# MCU.net
KiCad netlist of a schematic drawn in Altium Designer
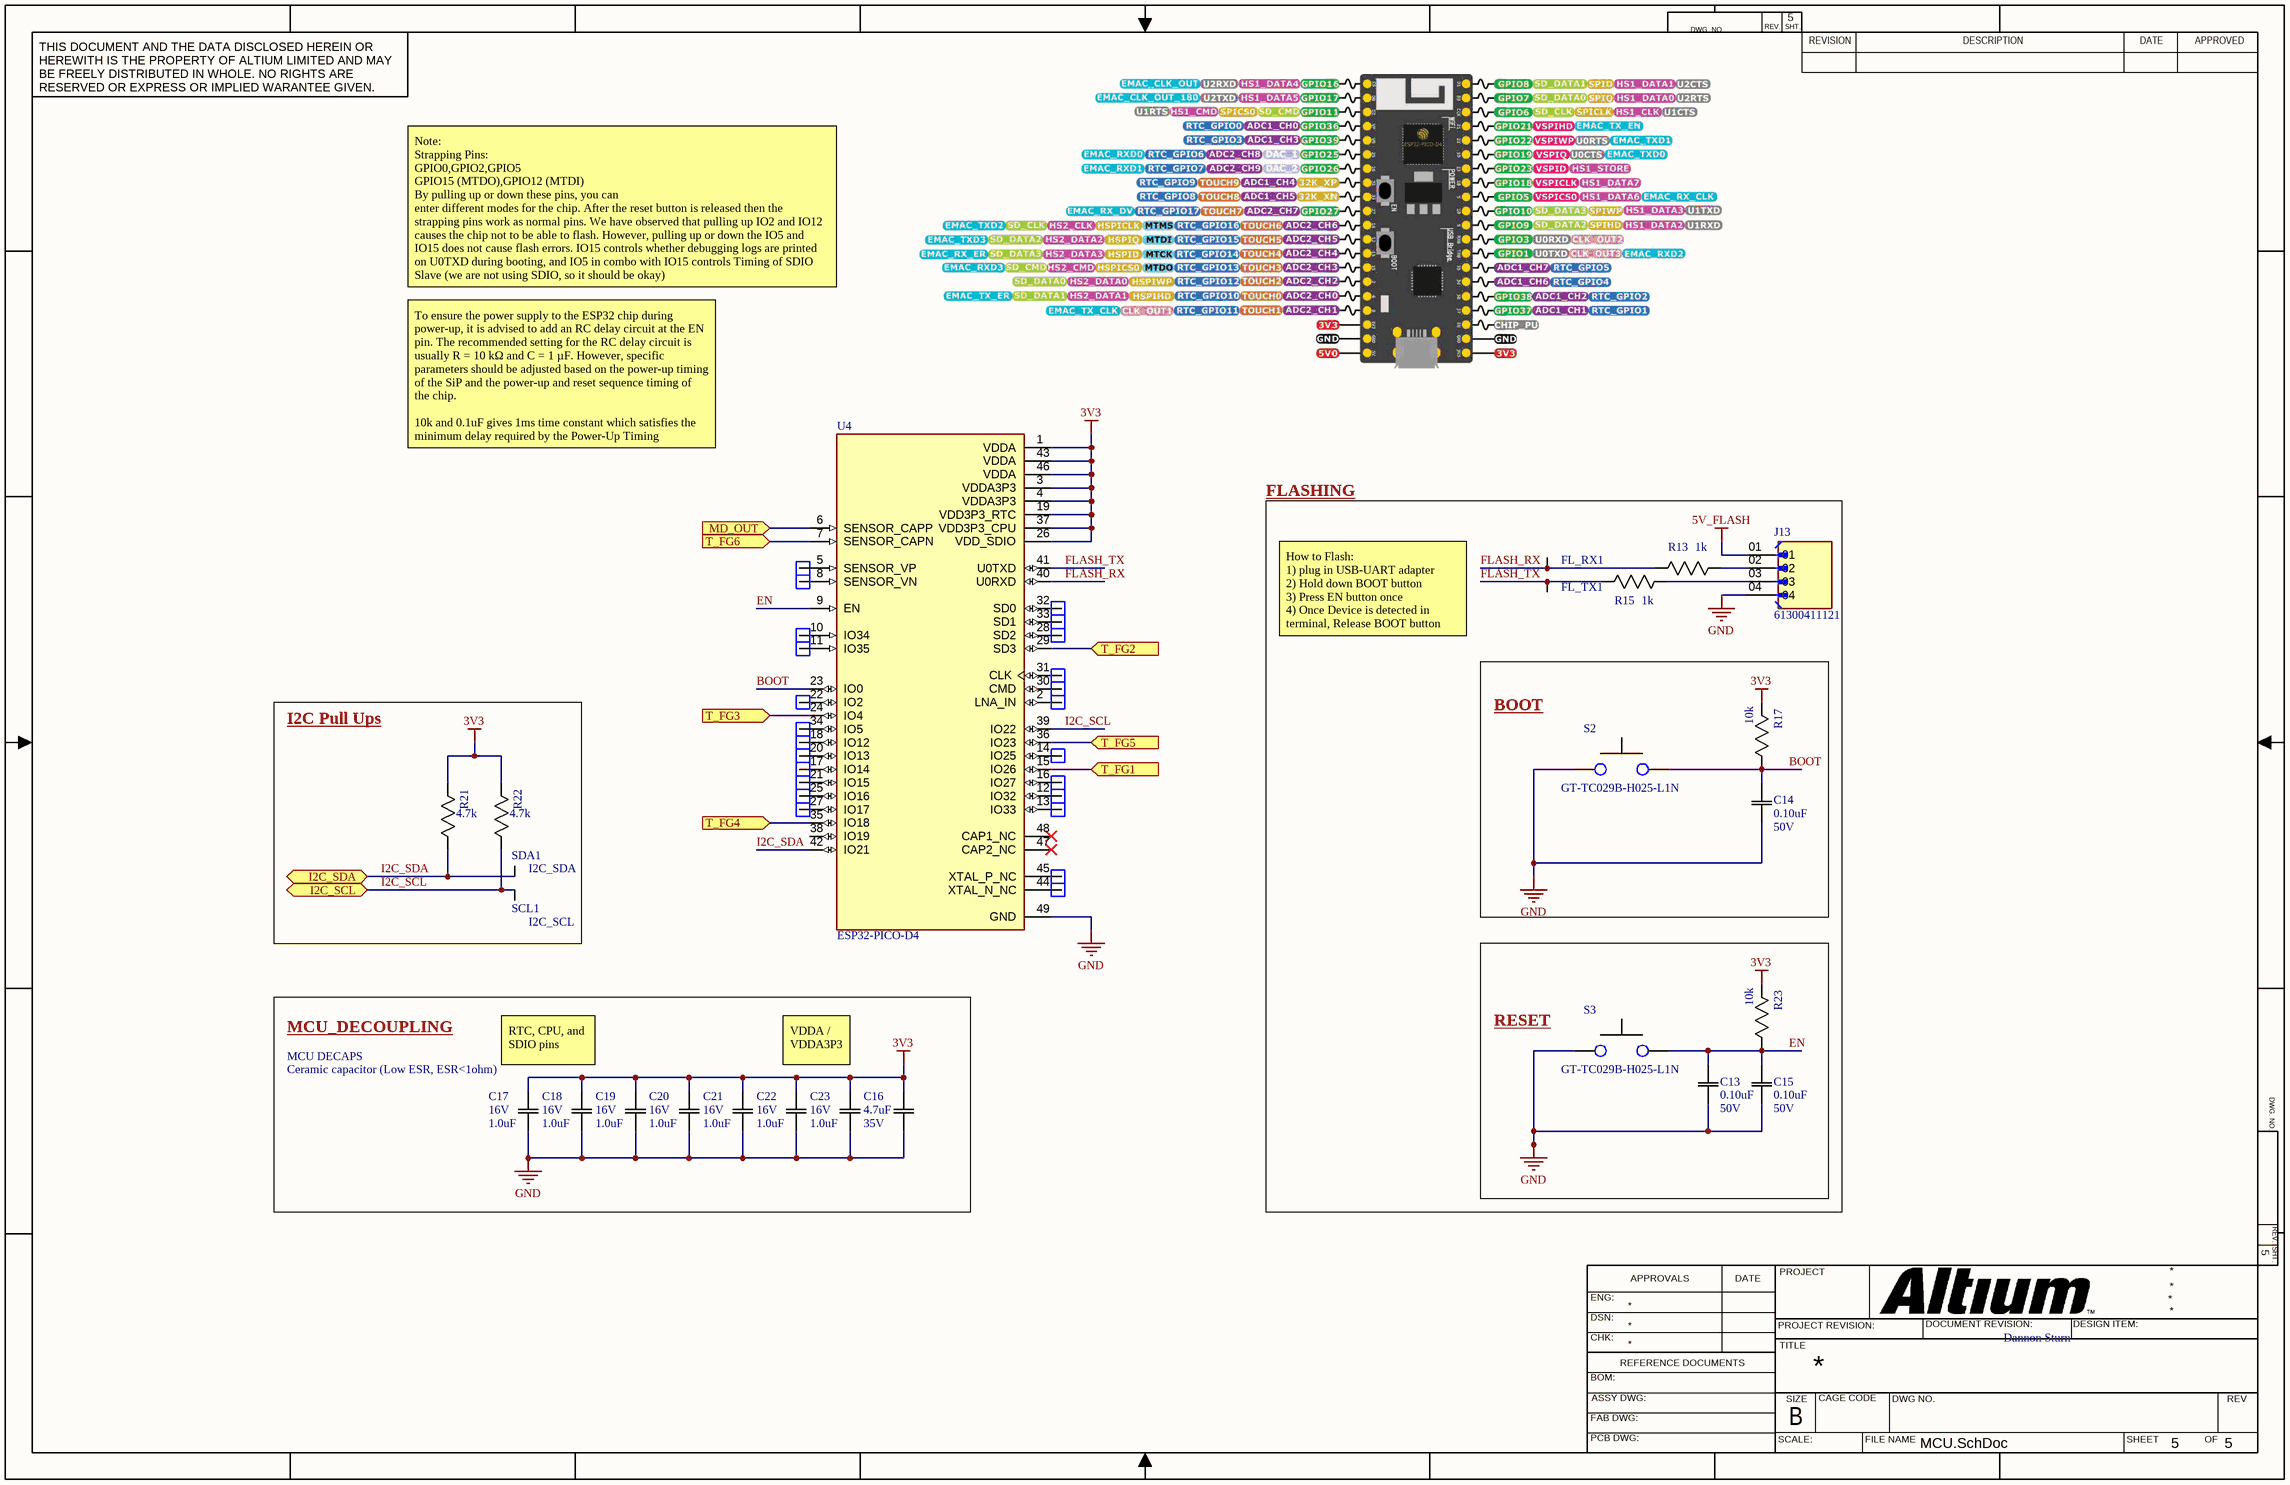
[diagram p0: MCU.SchDoc]

(export (version "E")
  (design (tool "Eeschema 10.0.6"))
  (components
    (comp (ref "1")
      (value "Breakout Pin 0603")
      (footprint "BreakoutPin 0603")
      (description "0603 breakout pad")
      (libsource (lib "IC_Library") (part "Breakout Pin 0603"))
    )
    (comp (ref "2")
      (value "Breakout Pin 0603")
      (footprint "BreakoutPin 0603")
      (description "0603 breakout pad")
      (libsource (lib "IC_Library") (part "Breakout Pin 0603"))
    )
    (comp (ref "3")
      (value "Breakout Pin 0603")
      (footprint "BreakoutPin 0603")
      (description "0603 breakout pad")
      (libsource (lib "IC_Library") (part "Breakout Pin 0603"))
    )
    (comp (ref "4")
      (value "Breakout Pin 0603")
      (footprint "BreakoutPin 0603")
      (description "0603 breakout pad")
      (libsource (lib "IC_Library") (part "Breakout Pin 0603"))
    )
    (comp (ref "5")
      (value "Breakout Pin 0603")
      (footprint "BreakoutPin 0603")
      (description "0603 breakout pad")
      (libsource (lib "IC_Library") (part "Breakout Pin 0603"))
    )
    (comp (ref "6")
      (value "Breakout Pin 0603")
      (footprint "BreakoutPin 0603")
      (description "0603 breakout pad")
      (libsource (lib "IC_Library") (part "Breakout Pin 0603"))
    )
    (comp (ref "7")
      (value "Breakout Pin 0603")
      (footprint "BreakoutPin 0603")
      (description "0603 breakout pad")
      (libsource (lib "IC_Library") (part "Breakout Pin 0603"))
    )
    (comp (ref "8")
      (value "Breakout Pin 0603")
      (footprint "BreakoutPin 0603")
      (description "0603 breakout pad")
      (libsource (lib "IC_Library") (part "Breakout Pin 0603"))
    )
    (comp (ref "9")
      (value "Breakout Pin 0603")
      (footprint "BreakoutPin 0603")
      (description "0603 breakout pad")
      (libsource (lib "IC_Library") (part "Breakout Pin 0603"))
    )
    (comp (ref "10")
      (value "Breakout Pin 0603")
      (footprint "BreakoutPin 0603")
      (description "0603 breakout pad")
      (libsource (lib "IC_Library") (part "Breakout Pin 0603"))
    )
    (comp (ref "11")
      (value "Breakout Pin 0603")
      (footprint "BreakoutPin 0603")
      (description "0603 breakout pad")
      (libsource (lib "IC_Library") (part "Breakout Pin 0603"))
    )
    (comp (ref "12")
      (value "Breakout Pin 0603")
      (footprint "BreakoutPin 0603")
      (description "0603 breakout pad")
      (libsource (lib "IC_Library") (part "Breakout Pin 0603"))
    )
    (comp (ref "13")
      (value "Breakout Pin 0603")
      (footprint "BreakoutPin 0603")
      (description "0603 breakout pad")
      (libsource (lib "IC_Library") (part "Breakout Pin 0603"))
    )
    (comp (ref "14")
      (value "Breakout Pin 0603")
      (footprint "BreakoutPin 0603")
      (description "0603 breakout pad")
      (libsource (lib "IC_Library") (part "Breakout Pin 0603"))
    )
    (comp (ref "15")
      (value "Breakout Pin 0603")
      (footprint "BreakoutPin 0603")
      (description "0603 breakout pad")
      (libsource (lib "IC_Library") (part "Breakout Pin 0603"))
    )
    (comp (ref "16")
      (value "Breakout Pin 0603")
      (footprint "BreakoutPin 0603")
      (description "0603 breakout pad")
      (libsource (lib "IC_Library") (part "Breakout Pin 0603"))
    )
    (comp (ref "17")
      (value "Breakout Pin 0603")
      (footprint "BreakoutPin 0603")
      (description "0603 breakout pad")
      (libsource (lib "IC_Library") (part "Breakout Pin 0603"))
    )
    (comp (ref "18")
      (value "Breakout Pin 0603")
      (footprint "BreakoutPin 0603")
      (description "0603 breakout pad")
      (libsource (lib "IC_Library") (part "Breakout Pin 0603"))
    )
    (comp (ref "19")
      (value "Breakout Pin 0603")
      (footprint "BreakoutPin 0603")
      (description "0603 breakout pad")
      (libsource (lib "IC_Library") (part "Breakout Pin 0603"))
    )
    (comp (ref "20")
      (value "Breakout Pin 0603")
      (footprint "BreakoutPin 0603")
      (description "0603 breakout pad")
      (libsource (lib "IC_Library") (part "Breakout Pin 0603"))
    )
    (comp (ref "21")
      (value "Breakout Pin 0603")
      (footprint "BreakoutPin 0603")
      (description "0603 breakout pad")
      (libsource (lib "IC_Library") (part "Breakout Pin 0603"))
    )
    (comp (ref "22")
      (value "Breakout Pin 0603")
      (footprint "BreakoutPin 0603")
      (description "0603 breakout pad")
      (libsource (lib "IC_Library") (part "Breakout Pin 0603"))
    )
    (comp (ref "23")
      (value "Breakout Pin 0603")
      (footprint "BreakoutPin 0603")
      (description "0603 breakout pad")
      (libsource (lib "IC_Library") (part "Breakout Pin 0603"))
    )
    (comp (ref "24")
      (value "Breakout Pin 0603")
      (footprint "BreakoutPin 0603")
      (description "0603 breakout pad")
      (libsource (lib "IC_Library") (part "Breakout Pin 0603"))
    )
    (comp (ref "C13")
      (value "0.10uF")
      (footprint "0603")
      (description "Default Symbol for Capacitors")
      (fields
        (field (name "RATING") "50V")
        (field (name "PART NUMBER") "CAP 0.1uF 50V")
        (field (name "TOLERANCE") "10%")
      )
      (libsource (lib "capacitor_library") (part "CAP_Default"))
    )
    (comp (ref "C14")
      (value "0.10uF")
      (footprint "0603")
      (description "Default Symbol for Capacitors")
      (fields
        (field (name "RATING") "50V")
        (field (name "PART NUMBER") "CAP 0.1uF 50V")
        (field (name "TOLERANCE") "10%")
      )
      (libsource (lib "capacitor_library") (part "CAP_Default"))
    )
    (comp (ref "C15")
      (value "0.10uF")
      (footprint "0805")
      (description "Default Symbol for Capacitors")
      (fields
        (field (name "RATING") "50V")
        (field (name "PART NUMBER") "CAP 0.1uF 50V")
        (field (name "TOLERANCE") "10%")
      )
      (libsource (lib "capacitor_library") (part "CAP_Default"))
    )
    (comp (ref "C16")
      (value "4.7uF")
      (footprint "0603")
      (description "CAP CER 4.7UF 35V X7R 0603/0805")
      (fields
        (field (name "TOLERANCE") "10%")
        (field (name "RATING") "35V")
        (field (name "PART NUMBER") "CAP 4.7uF 35V")
      )
      (libsource (lib "capacitor_library") (part "CAP 4.7uF 35V"))
    )
    (comp (ref "C17")
      (value "1.0uF")
      (footprint "0603")
      (description "CAP CER 1.0UF 16V X5R 0603/0805")
      (fields
        (field (name "TOLERANCE") "10%")
        (field (name "RATING") "16V")
        (field (name "PART NUMBER") "CAP 1.0uF 16V")
      )
      (libsource (lib "capacitor_library") (part "CAP 1.0uF 16V"))
    )
    (comp (ref "C18")
      (value "1.0uF")
      (footprint "0603")
      (description "CAP CER 1.0UF 16V X5R 0603/0805")
      (fields
        (field (name "TOLERANCE") "10%")
        (field (name "RATING") "16V")
        (field (name "PART NUMBER") "CAP 1.0uF 16V")
      )
      (libsource (lib "capacitor_library") (part "CAP 1.0uF 16V"))
    )
    (comp (ref "C19")
      (value "1.0uF")
      (footprint "0603")
      (description "CAP CER 1.0UF 16V X5R 0603/0805")
      (fields
        (field (name "TOLERANCE") "10%")
        (field (name "RATING") "16V")
        (field (name "PART NUMBER") "CAP 1.0uF 16V")
      )
      (libsource (lib "capacitor_library") (part "CAP 1.0uF 16V"))
    )
    (comp (ref "C20")
      (value "1.0uF")
      (footprint "0603")
      (description "CAP CER 1.0UF 16V X5R 0603/0805")
      (fields
        (field (name "TOLERANCE") "10%")
        (field (name "RATING") "16V")
        (field (name "PART NUMBER") "CAP 1.0uF 16V")
      )
      (libsource (lib "capacitor_library") (part "CAP 1.0uF 16V"))
    )
    (comp (ref "C21")
      (value "1.0uF")
      (footprint "0603")
      (description "CAP CER 1.0UF 16V X5R 0603/0805")
      (fields
        (field (name "TOLERANCE") "10%")
        (field (name "RATING") "16V")
        (field (name "PART NUMBER") "CAP 1.0uF 16V")
      )
      (libsource (lib "capacitor_library") (part "CAP 1.0uF 16V"))
    )
    (comp (ref "C22")
      (value "1.0uF")
      (footprint "0603")
      (description "CAP CER 1.0UF 16V X5R 0603/0805")
      (fields
        (field (name "TOLERANCE") "10%")
        (field (name "RATING") "16V")
        (field (name "PART NUMBER") "CAP 1.0uF 16V")
      )
      (libsource (lib "capacitor_library") (part "CAP 1.0uF 16V"))
    )
    (comp (ref "C23")
      (value "1.0uF")
      (footprint "0603")
      (description "CAP CER 1.0UF 16V X5R 0603/0805")
      (fields
        (field (name "TOLERANCE") "10%")
        (field (name "RATING") "16V")
        (field (name "PART NUMBER") "CAP 1.0uF 16V")
      )
      (libsource (lib "capacitor_library") (part "CAP 1.0uF 16V"))
    )
    (comp (ref "FL_RX1")
      (value "Test Point (Via)")
      (footprint "TP")
      (libsource (lib "IC_Library") (part "Test Point (Via)"))
    )
    (comp (ref "FL_TX1")
      (value "Test Point (Via)")
      (footprint "TP")
      (libsource (lib "IC_Library") (part "Test Point (Via)"))
    )
    (comp (ref "J13")
      (value "61300411121")
      (footprint "WURTH_61300411121")
      (description "Connector Header Through Hole 4 position 0.100 (2.54mm)")
      (fields (field (name "MF") "Wurth Electronics"))
      (libsource (lib "61300411121") (part "61300411121"))
    )
    (comp (ref "R13")
      (value "1k")
      (footprint "0603")
      (description "Default Resistor Symbol")
      (fields (field (name "TOLERANCE") "1%") (field (name "PART NUMBER") "RES 1k 1/8W"))
      (libsource (lib "Resistor_Library") (part "RES_DEFAULT"))
    )
    (comp (ref "R15")
      (value "1k")
      (footprint "0603")
      (description "Default Resistor Symbol")
      (fields (field (name "TOLERANCE") "1%") (field (name "PART NUMBER") "RES 1k 1/8W"))
      (libsource (lib "") (part "RES_DEFAULT_1"))
    )
    (comp (ref "R17")
      (value "10k")
      (footprint "0603")
      (description "RES SMD 10K OHM 5% 1/8W 0603")
      (fields (field (name "TOLERANCE") "5%") (field (name "PART NUMBER") "RES 10k 1/8W - 5%"))
      (libsource (lib "Resistor_Library") (part "RES 10k 1/8W 5%"))
    )
    (comp (ref "R21")
      (value "4.7k")
      (footprint "0805")
      (description "Default Resistor Symbol")
      (fields (field (name "TOLERANCE") "1%") (field (name "PART NUMBER") "RES 4.7k 1/8W - 1%"))
      (libsource (lib "") (part "RES_DEFAULT_1"))
    )
    (comp (ref "R22")
      (value "4.7k")
      (footprint "0805")
      (description "Default Resistor Symbol")
      (fields (field (name "TOLERANCE") "1%") (field (name "PART NUMBER") "RES 4.7k 1/8W - 1%"))
      (libsource (lib "") (part "RES_DEFAULT_1"))
    )
    (comp (ref "R23")
      (value "10k")
      (footprint "0603")
      (description "RES SMD 10K OHM 5% 1/8W 0603")
      (fields (field (name "TOLERANCE") "5%") (field (name "PART NUMBER") "RES 10k 1/8W - 5%"))
      (libsource (lib "Resistor_Library") (part "RES 10k 1/8W 5%"))
    )
    (comp (ref "S2")
      (value "GT-TC029B-H025-L1N")
      (footprint "SW_EVP-AWCD4A")
      (description "JLC Supplied: 50mA 3.9mm 100MΩ 100,000 Times 12V 250gf 2.9mm 2.5mm Round Button")
      (fields (field (name "MP") "EVP-AWCD4A"))
      (libsource (lib "GT-TC029B-H025-L1N") (part "GT-TC029B-H025-L1N"))
    )
    (comp (ref "S3")
      (value "GT-TC029B-H025-L1N")
      (footprint "SW_EVP-AWCD4A")
      (description "JLC Supplied: 50mA 3.9mm 100MΩ 100,000 Times 12V 250gf 2.9mm 2.5mm Round Button")
      (fields (field (name "MP") "EVP-AWCD4A"))
      (libsource (lib "GT-TC029B-H025-L1N") (part "GT-TC029B-H025-L1N"))
    )
    (comp (ref "SCL1")
      (value "I2C_SCL")
      (footprint "TP")
      (fields (field (name "PART NUMBER") "Test Point (Via)"))
      (libsource (lib "IC_Library") (part "Test Point (Via)"))
    )
    (comp (ref "SDA1")
      (value "I2C_SDA")
      (footprint "TP")
      (fields (field (name "PART NUMBER") "Test Point (Via)"))
      (libsource (lib "IC_Library") (part "Test Point (Via)"))
    )
    (comp (ref "U4")
      (value "ESP32-PICO-D4")
      (footprint "PQFN50P700X700X104-49N - BigPads")
      (description "RX TXRX MOD WIFI SURFACE MOUNT")
      (fields (field (name "MF") "Espressif Systems"))
      (libsource (lib "IC_Library") (part "ESP32-PICO-D4"))
    )
  )
  (nets
    (net (code "1") (name "/BOOT") (class "Default")
      (node (ref "C14") (pin "2") (pinfunction "C2_2") (pintype "passive"))
      (node (ref "R17") (pin "1") (pinfunction "R1_1") (pintype "passive"))
      (node (ref "S2") (pin "2") (pinfunction "2_2") (pintype "passive"))
      (node (ref "U4") (pin "23") (pinfunction "IO0_23") (pintype "bidirectional"))
    )
    (net (code "2") (name "/EN") (class "Default")
      (node (ref "C13") (pin "2") (pinfunction "C2_2") (pintype "passive"))
      (node (ref "C15") (pin "2") (pinfunction "C2_2") (pintype "passive"))
      (node (ref "R23") (pin "1") (pinfunction "R1_1") (pintype "passive"))
      (node (ref "S3") (pin "2") (pinfunction "2_2") (pintype "passive"))
      (node (ref "U4") (pin "9") (pinfunction "EN_9") (pintype "input"))
    )
    (net (code "3") (name "/FLASH_RX") (class "Default")
      (node (ref "FL_RX1") (pin "1") (pinfunction "1_1") (pintype "passive"))
      (node (ref "R13") (pin "2") (pinfunction "R2_2") (pintype "passive"))
      (node (ref "U4") (pin "40") (pinfunction "U0RXD_40") (pintype "bidirectional"))
    )
    (net (code "4") (name "/FLASH_TX") (class "Default")
      (node (ref "FL_TX1") (pin "1") (pinfunction "1_1") (pintype "passive"))
      (node (ref "R15") (pin "2") (pinfunction "R2_2") (pintype "passive"))
      (node (ref "U4") (pin "41") (pinfunction "U0TXD_41") (pintype "bidirectional"))
    )
    (net (code "5") (name "/I2C_SCL") (class "Default")
      (node (ref "R22") (pin "1") (pinfunction "R1_1") (pintype "passive"))
      (node (ref "SCL1") (pin "1") (pinfunction "1_1") (pintype "passive"))
      (node (ref "U4") (pin "39") (pinfunction "IO22_39") (pintype "bidirectional"))
    )
    (net (code "6") (name "/I2C_SDA") (class "Default")
      (node (ref "R21") (pin "1") (pinfunction "R1_1") (pintype "passive"))
      (node (ref "SDA1") (pin "1") (pinfunction "1_1") (pintype "passive"))
      (node (ref "U4") (pin "42") (pinfunction "IO21_42") (pintype "bidirectional"))
    )
    (net (code "7") (name "/MD_OUT") (class "Default")
      (node (ref "U4") (pin "6") (pinfunction "SENSOR_CAPP_6") (pintype "input"))
    )
    (net (code "8") (name "/T_FG1") (class "Default")
      (node (ref "U4") (pin "15") (pinfunction "IO26_15") (pintype "bidirectional"))
    )
    (net (code "9") (name "/T_FG2") (class "Default")
      (node (ref "U4") (pin "29") (pinfunction "SD3_29") (pintype "bidirectional"))
    )
    (net (code "10") (name "/T_FG3") (class "Default")
      (node (ref "U4") (pin "24") (pinfunction "IO4_24") (pintype "bidirectional"))
    )
    (net (code "11") (name "/T_FG4") (class "Default")
      (node (ref "U4") (pin "35") (pinfunction "IO18_35") (pintype "bidirectional"))
    )
    (net (code "12") (name "/T_FG5") (class "Default")
      (node (ref "U4") (pin "36") (pinfunction "IO23_36") (pintype "bidirectional"))
    )
    (net (code "13") (name "/T_FG6") (class "Default")
      (node (ref "U4") (pin "7") (pinfunction "SENSOR_CAPN_7") (pintype "input"))
    )
    (net (code "14") (name "3V3") (class "Default")
      (node (ref "C16") (pin "2") (pinfunction "C2_2") (pintype "passive"))
      (node (ref "C17") (pin "2") (pinfunction "C2_2") (pintype "passive"))
      (node (ref "C18") (pin "2") (pinfunction "C2_2") (pintype "passive"))
      (node (ref "C19") (pin "2") (pinfunction "C2_2") (pintype "passive"))
      (node (ref "C20") (pin "2") (pinfunction "C2_2") (pintype "passive"))
      (node (ref "C21") (pin "2") (pinfunction "C2_2") (pintype "passive"))
      (node (ref "C22") (pin "2") (pinfunction "C2_2") (pintype "passive"))
      (node (ref "C23") (pin "2") (pinfunction "C2_2") (pintype "passive"))
      (node (ref "R17") (pin "2") (pinfunction "R2_2") (pintype "passive"))
      (node (ref "R21") (pin "2") (pinfunction "R2_2") (pintype "passive"))
      (node (ref "R22") (pin "2") (pinfunction "R2_2") (pintype "passive"))
      (node (ref "R23") (pin "2") (pinfunction "R2_2") (pintype "passive"))
      (node (ref "U4") (pin "1") (pinfunction "VDDA_1") (pintype "power_in"))
      (node (ref "U4") (pin "19") (pinfunction "VDD3P3_RTC_19") (pintype "power_in"))
      (node (ref "U4") (pin "26") (pinfunction "VDD_SDIO_26") (pintype "power_in"))
      (node (ref "U4") (pin "3") (pinfunction "VDDA3P3_3") (pintype "power_in"))
      (node (ref "U4") (pin "37") (pinfunction "VDD3P3_CPU_37") (pintype "power_in"))
      (node (ref "U4") (pin "4") (pinfunction "VDDA3P3_4") (pintype "power_in"))
      (node (ref "U4") (pin "43") (pinfunction "VDDA_43") (pintype "power_in"))
      (node (ref "U4") (pin "46") (pinfunction "VDDA_46") (pintype "power_in"))
    )
    (net (code "15") (name "5V_FLASH") (class "Default")
      (node (ref "J13") (pin "01") (pinfunction "01_01") (pintype "passive"))
    )
    (net (code "16") (name "GND") (class "Default")
      (node (ref "C13") (pin "1") (pinfunction "C1_1") (pintype "passive"))
      (node (ref "C14") (pin "1") (pinfunction "C1_1") (pintype "passive"))
      (node (ref "C15") (pin "1") (pinfunction "C1_1") (pintype "passive"))
      (node (ref "C16") (pin "1") (pinfunction "C1_1") (pintype "passive"))
      (node (ref "C17") (pin "1") (pinfunction "C1_1") (pintype "passive"))
      (node (ref "C18") (pin "1") (pinfunction "C1_1") (pintype "passive"))
      (node (ref "C19") (pin "1") (pinfunction "C1_1") (pintype "passive"))
      (node (ref "C20") (pin "1") (pinfunction "C1_1") (pintype "passive"))
      (node (ref "C21") (pin "1") (pinfunction "C1_1") (pintype "passive"))
      (node (ref "C22") (pin "1") (pinfunction "C1_1") (pintype "passive"))
      (node (ref "C23") (pin "1") (pinfunction "C1_1") (pintype "passive"))
      (node (ref "J13") (pin "04") (pinfunction "04_04") (pintype "passive"))
      (node (ref "S2") (pin "1") (pinfunction "1_1") (pintype "passive"))
      (node (ref "S3") (pin "1") (pinfunction "1_1") (pintype "passive"))
      (node (ref "U4") (pin "49") (pinfunction "GND_49") (pintype "power_in"))
    )
    (net (code "17") (name "Net-(1-BRKOUT)") (class "Default")
      (node (ref "1") (pin "1") (pinfunction "BRKOUT_1") (pintype "passive"))
      (node (ref "U4") (pin "5") (pinfunction "SENSOR_VP_5") (pintype "input"))
    )
    (net (code "18") (name "Net-(2-BRKOUT)") (class "Default")
      (node (ref "2") (pin "1") (pinfunction "BRKOUT_1") (pintype "passive"))
      (node (ref "U4") (pin "8") (pinfunction "SENSOR_VN_8") (pintype "input"))
    )
    (net (code "19") (name "Net-(3-BRKOUT)") (class "Default")
      (node (ref "3") (pin "1") (pinfunction "BRKOUT_1") (pintype "passive"))
      (node (ref "U4") (pin "10") (pinfunction "IO34_10") (pintype "input"))
    )
    (net (code "20") (name "Net-(4-BRKOUT)") (class "Default")
      (node (ref "4") (pin "1") (pinfunction "BRKOUT_1") (pintype "passive"))
      (node (ref "U4") (pin "32") (pinfunction "SD0_32") (pintype "bidirectional"))
    )
    (net (code "21") (name "Net-(5-BRKOUT)") (class "Default")
      (node (ref "5") (pin "1") (pinfunction "BRKOUT_1") (pintype "passive"))
      (node (ref "U4") (pin "11") (pinfunction "IO35_11") (pintype "input"))
    )
    (net (code "22") (name "Net-(6-BRKOUT)") (class "Default")
      (node (ref "6") (pin "1") (pinfunction "BRKOUT_1") (pintype "passive"))
      (node (ref "U4") (pin "33") (pinfunction "SD1_33") (pintype "bidirectional"))
    )
    (net (code "23") (name "Net-(7-BRKOUT)") (class "Default")
      (node (ref "7") (pin "1") (pinfunction "BRKOUT_1") (pintype "passive"))
      (node (ref "U4") (pin "22") (pinfunction "IO2_22") (pintype "bidirectional"))
    )
    (net (code "24") (name "Net-(8-BRKOUT)") (class "Default")
      (node (ref "8") (pin "1") (pinfunction "BRKOUT_1") (pintype "passive"))
      (node (ref "U4") (pin "31") (pinfunction "CLK_31") (pintype "bidirectional"))
    )
    (net (code "25") (name "Net-(9-BRKOUT)") (class "Default")
      (node (ref "9") (pin "1") (pinfunction "BRKOUT_1") (pintype "passive"))
      (node (ref "U4") (pin "30") (pinfunction "CMD_30") (pintype "bidirectional"))
    )
    (net (code "26") (name "Net-(10-BRKOUT)") (class "Default")
      (node (ref "10") (pin "1") (pinfunction "BRKOUT_1") (pintype "passive"))
      (node (ref "U4") (pin "2") (pinfunction "LNA_IN_2") (pintype "bidirectional"))
    )
    (net (code "27") (name "Net-(11-BRKOUT)") (class "Default")
      (node (ref "11") (pin "1") (pinfunction "BRKOUT_1") (pintype "passive"))
      (node (ref "U4") (pin "18") (pinfunction "IO12_18") (pintype "bidirectional"))
    )
    (net (code "28") (name "Net-(12-BRKOUT)") (class "Default")
      (node (ref "12") (pin "1") (pinfunction "BRKOUT_1") (pintype "passive"))
      (node (ref "U4") (pin "28") (pinfunction "SD2_28") (pintype "bidirectional"))
    )
    (net (code "29") (name "Net-(13-BRKOUT)") (class "Default")
      (node (ref "13") (pin "1") (pinfunction "BRKOUT_1") (pintype "passive"))
      (node (ref "U4") (pin "25") (pinfunction "IO16_25") (pintype "bidirectional"))
    )
    (net (code "30") (name "Net-(14-BRKOUT)") (class "Default")
      (node (ref "14") (pin "1") (pinfunction "BRKOUT_1") (pintype "passive"))
      (node (ref "U4") (pin "27") (pinfunction "IO17_27") (pintype "bidirectional"))
    )
    (net (code "31") (name "Net-(15-BRKOUT)") (class "Default")
      (node (ref "15") (pin "1") (pinfunction "BRKOUT_1") (pintype "passive"))
      (node (ref "U4") (pin "34") (pinfunction "IO5_34") (pintype "bidirectional"))
    )
    (net (code "32") (name "Net-(16-BRKOUT)") (class "Default")
      (node (ref "16") (pin "1") (pinfunction "BRKOUT_1") (pintype "passive"))
      (node (ref "U4") (pin "45") (pinfunction "XTAL_P_NC_45") (pintype "passive"))
    )
    (net (code "33") (name "Net-(17-BRKOUT)") (class "Default")
      (node (ref "17") (pin "1") (pinfunction "BRKOUT_1") (pintype "passive"))
      (node (ref "U4") (pin "44") (pinfunction "XTAL_N_NC_44") (pintype "passive"))
    )
    (net (code "34") (name "Net-(18-BRKOUT)") (class "Default")
      (node (ref "18") (pin "1") (pinfunction "BRKOUT_1") (pintype "passive"))
      (node (ref "U4") (pin "20") (pinfunction "IO13_20") (pintype "bidirectional"))
    )
    (net (code "35") (name "Net-(19-BRKOUT)") (class "Default")
      (node (ref "19") (pin "1") (pinfunction "BRKOUT_1") (pintype "passive"))
      (node (ref "U4") (pin "17") (pinfunction "IO14_17") (pintype "bidirectional"))
    )
    (net (code "36") (name "Net-(20-BRKOUT)") (class "Default")
      (node (ref "20") (pin "1") (pinfunction "BRKOUT_1") (pintype "passive"))
      (node (ref "U4") (pin "21") (pinfunction "IO15_21") (pintype "bidirectional"))
    )
    (net (code "37") (name "Net-(21-BRKOUT)") (class "Default")
      (node (ref "21") (pin "1") (pinfunction "BRKOUT_1") (pintype "passive"))
      (node (ref "U4") (pin "16") (pinfunction "IO27_16") (pintype "bidirectional"))
    )
    (net (code "38") (name "Net-(22-BRKOUT)") (class "Default")
      (node (ref "22") (pin "1") (pinfunction "BRKOUT_1") (pintype "passive"))
      (node (ref "U4") (pin "12") (pinfunction "IO32_12") (pintype "bidirectional"))
    )
    (net (code "39") (name "Net-(23-BRKOUT)") (class "Default")
      (node (ref "23") (pin "1") (pinfunction "BRKOUT_1") (pintype "passive"))
      (node (ref "U4") (pin "13") (pinfunction "IO33_13") (pintype "bidirectional"))
    )
    (net (code "40") (name "Net-(24-BRKOUT)") (class "Default")
      (node (ref "24") (pin "1") (pinfunction "BRKOUT_1") (pintype "passive"))
      (node (ref "U4") (pin "14") (pinfunction "IO25_14") (pintype "bidirectional"))
    )
    (net (code "41") (name "Net-(R13-R1)") (class "Default")
      (node (ref "J13") (pin "02") (pinfunction "02_02") (pintype "passive"))
      (node (ref "R13") (pin "1") (pinfunction "R1_1") (pintype "passive"))
    )
    (net (code "42") (name "Net-(R15-R1)") (class "Default")
      (node (ref "J13") (pin "03") (pinfunction "03_03") (pintype "passive"))
      (node (ref "R15") (pin "1") (pinfunction "R1_1") (pintype "passive"))
    )
    (net (code "43") (name "unconnected-(U4-CAP1_NC-Pad48)") (class "Default")
      (node (ref "U4") (pin "48") (pinfunction "CAP1_NC_48") (pintype "passive+no_connect"))
    )
    (net (code "44") (name "unconnected-(U4-CAP2_NC-Pad47)") (class "Default")
      (node (ref "U4") (pin "47") (pinfunction "CAP2_NC_47") (pintype "passive+no_connect"))
    )
    (net (code "45") (name "unconnected-(U4-IO19-Pad38)") (class "Default")
      (node (ref "U4") (pin "38") (pinfunction "IO19_38") (pintype "bidirectional"))
    )
  )
)
